# lm2676.net
KiCad netlist of a schematic drawn in EAGLE
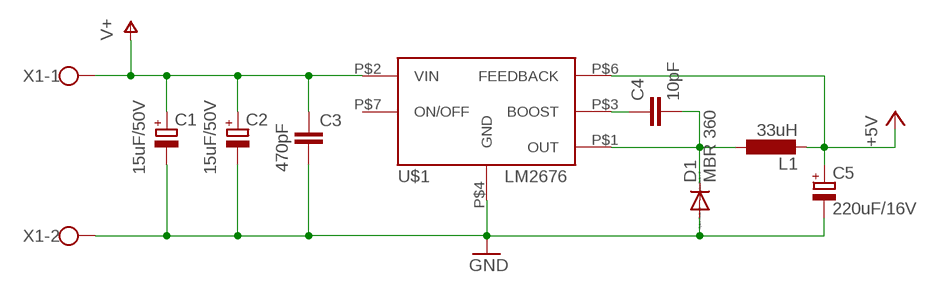
[diagram p0: schematic, sheet 1]

(export (version "E")
  (design (tool "Eeschema 10.0.6"))
  (components
    (comp (ref "C1")
      (value "15uF/50V")
      (footprint "eagle-import:E2-5")
      (libsource (lib "eagle-import") (part "CPOL-EUE2-5"))
    )
    (comp (ref "C2")
      (value "15uF/50V")
      (footprint "eagle-import:E2-5")
      (libsource (lib "eagle-import") (part "CPOL-EUE2-5"))
    )
    (comp (ref "C3")
      (value "470pF")
      (footprint "eagle-import:C025-025X050")
      (libsource (lib "eagle-import") (part "C-EU025-025X050"))
    )
    (comp (ref "C4")
      (value "10pF")
      (footprint "eagle-import:C025-025X050")
      (libsource (lib "eagle-import") (part "C-EU025-025X050"))
    )
    (comp (ref "C5")
      (value "220uF/16V")
      (footprint "eagle-import:E2,5-6")
      (libsource (lib "eagle-import") (part "CPOL-EUE2.5-6"))
    )
    (comp (ref "D1")
      (value "MBR 360")
      (footprint "eagle-import:DO201-15")
      (libsource (lib "eagle-import") (part "1N5400"))
    )
    (comp (ref "L1")
      (value "33uH")
      (footprint "eagle-import:TFI0510")
      (libsource (lib "eagle-import") (part "L-EUTFI0510"))
    )
    (comp (ref "U$1")
      (value "LM2676")
      (footprint "eagle-import:LM2676")
      (libsource (lib "eagle-import") (part "LM2676"))
    )
    (comp (ref "X1")
      (value "W237-102")
      (footprint "eagle-import:W237-102")
      (fields (field (name "MPN") "237-102"))
      (libsource (lib "eagle-import") (part "W237-102"))
    )
  )
  (nets
    (net (code "1") (name "+5V") (class "Default")
      (node (ref "C5") (pin "+") (pinfunction "+_+") (pintype "passive"))
      (node (ref "L1") (pin "2") (pinfunction "2_2") (pintype "passive"))
      (node (ref "U$1") (pin "P$6") (pinfunction "FEEDBACK_P$6") (pintype "bidirectional"))
    )
    (net (code "2") (name "GND") (class "Default")
      (node (ref "C1") (pin "-") (pinfunction "-_-") (pintype "passive"))
      (node (ref "C2") (pin "-") (pinfunction "-_-") (pintype "passive"))
      (node (ref "C3") (pin "2") (pinfunction "2_2") (pintype "passive"))
      (node (ref "C5") (pin "-") (pinfunction "-_-") (pintype "passive"))
      (node (ref "D1") (pin "A") (pinfunction "A_A") (pintype "passive"))
      (node (ref "U$1") (pin "P$4") (pinfunction "GND_P$4") (pintype "bidirectional"))
      (node (ref "X1") (pin "2") (pinfunction "KL_2") (pintype "passive"))
    )
    (net (code "3") (name "Net-(U$1-BOOST)") (class "Default")
      (node (ref "C4") (pin "1") (pinfunction "1_1") (pintype "passive"))
      (node (ref "U$1") (pin "P$3") (pinfunction "BOOST_P$3") (pintype "bidirectional"))
    )
    (net (code "4") (name "Net-(U$1-OUT)") (class "Default")
      (node (ref "C4") (pin "2") (pinfunction "2_2") (pintype "passive"))
      (node (ref "D1") (pin "C") (pinfunction "C_C") (pintype "passive"))
      (node (ref "L1") (pin "1") (pinfunction "1_1") (pintype "passive"))
      (node (ref "U$1") (pin "P$1") (pinfunction "OUT_P$1") (pintype "bidirectional"))
    )
    (net (code "5") (name "V+") (class "Default")
      (node (ref "C1") (pin "+") (pinfunction "+_+") (pintype "passive"))
      (node (ref "C2") (pin "+") (pinfunction "+_+") (pintype "passive"))
      (node (ref "C3") (pin "1") (pinfunction "1_1") (pintype "passive"))
      (node (ref "U$1") (pin "P$2") (pinfunction "VIN_P$2") (pintype "bidirectional"))
      (node (ref "X1") (pin "1") (pinfunction "KL_1") (pintype "passive"))
    )
    (net (code "6") (name "unconnected-(U$1-ON{slash}OFF-PadP$7)") (class "Default")
      (node (ref "U$1") (pin "P$7") (pinfunction "ON/OFF_P$7") (pintype "bidirectional"))
    )
  )
)
